# tsl2591.net
KiCad netlist of a schematic drawn in EAGLE
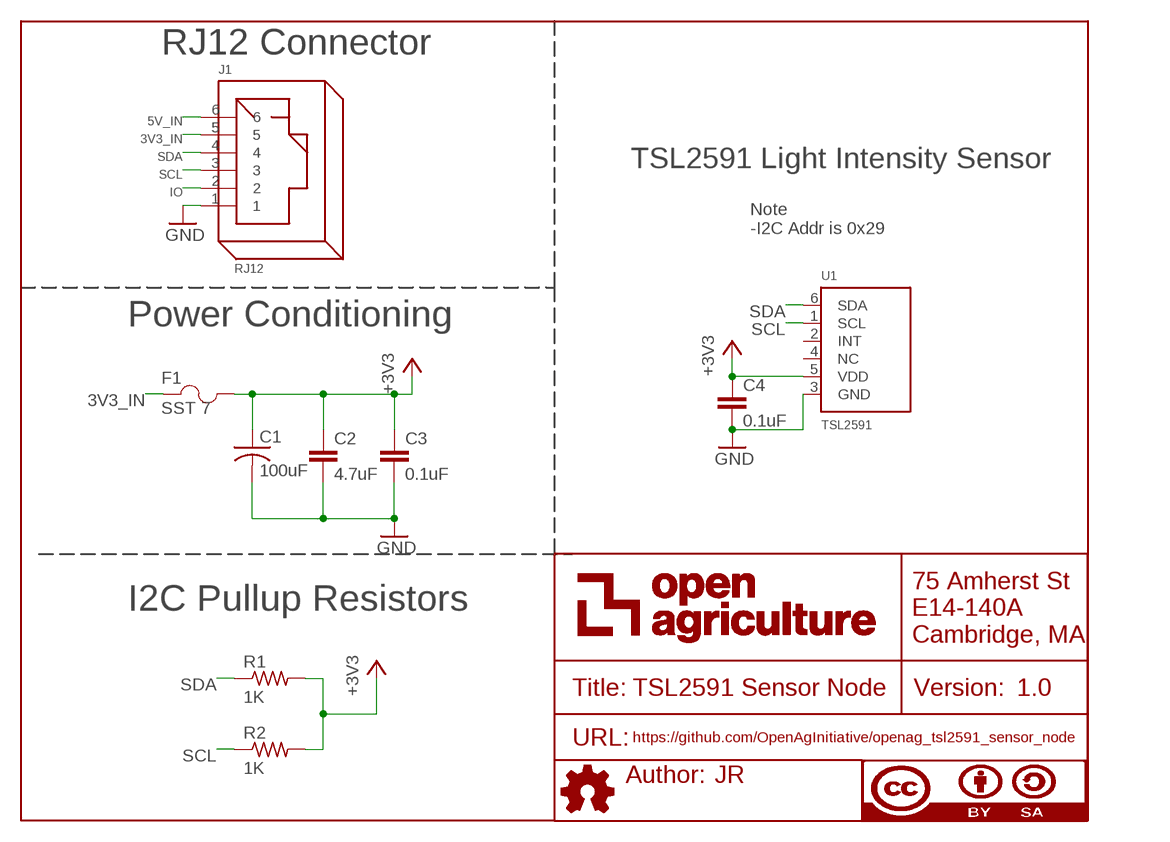
[diagram p0: schematic, sheet 1]

(export (version "E")
  (design (tool "Eeschema 10.0.6"))
  (components
    (comp (ref "C1")
      (value "100uF")
      (footprint "eagle-import:EEE-1HA101UP")
      (libsource (lib "eagle-import") (part "100UF-EEE-1HA101UP"))
    )
    (comp (ref "C2")
      (value "4.7uF")
      (footprint "eagle-import:C0805")
      (libsource (lib "eagle-import") (part "4.7UF-CL21A475KBQNNNE"))
    )
    (comp (ref "C3")
      (value "0.1uF")
      (footprint "eagle-import:C0603")
      (libsource (lib "eagle-import") (part "0.1UF-C0603C104K5RACTU"))
    )
    (comp (ref "C4")
      (value "0.1uF")
      (footprint "eagle-import:C0603")
      (libsource (lib "eagle-import") (part "0.1UF-C0603C104K5RACTU"))
    )
    (comp (ref "F1")
      (value "SST 7")
      (footprint "eagle-import:SS")
      (libsource (lib "eagle-import") (part "SST_7"))
    )
    (comp (ref "FRAME1")
      (value "DOCFIELD")
      (footprint "eagle-import:DOCFIELD")
      (description "APDS-9250 RGB/UV + Ambient Light Intensity Sensor Node")
      (fields
        (field (name "TITLE") "Example Template")
        (field (name "AUTHOR") "XX")
        (field (name "VER") "1.0")
        (field (name "URL") "https://github.com/OpenAgInitiative/openag_eagle_template")
        (field (name "AUTHOR_1") "JR")
        (field (name "TITLE_1") "TSL2591 Sensor Node")
        (field (name "URL_1") "https://github.com/OpenAgInitiative/openag_tsl2591_sensor_node")
      )
      (libsource (lib "eagle-import") (part "DOCFIELD"))
    )
    (comp (ref "J1")
      (value "RJ12")
      (footprint "eagle-import:RJ12")
      (libsource (lib "eagle-import") (part "A-2004-1-4-LP-N-R"))
    )
    (comp (ref "R1")
      (value "1K")
      (footprint "eagle-import:RC0603N")
      (libsource (lib "eagle-import") (part "1K-ERJ-PB3D1001V"))
    )
    (comp (ref "R2")
      (value "1K")
      (footprint "eagle-import:RC0603N")
      (libsource (lib "eagle-import") (part "1K-ERJ-PB3D1001V"))
    )
    (comp (ref "U1")
      (value "TSL2591")
      (footprint "eagle-import:DFN6_TAOS")
      (libsource (lib "eagle-import") (part "TSL25911FN"))
    )
  )
  (nets
    (net (code "1") (name "+3V3") (class "Default")
      (node (ref "C1") (pin "+") (pinfunction "1(+)_+") (pintype "passive"))
      (node (ref "C2") (pin "1") (pinfunction "1_1") (pintype "passive"))
      (node (ref "C3") (pin "1") (pinfunction "1_1") (pintype "passive"))
      (node (ref "C4") (pin "1") (pinfunction "1_1") (pintype "passive"))
      (node (ref "F1") (pin "2") (pinfunction "2_2") (pintype "passive"))
      (node (ref "R1") (pin "2") (pinfunction "2_2") (pintype "passive"))
      (node (ref "R2") (pin "2") (pinfunction "2_2") (pintype "passive"))
      (node (ref "U1") (pin "5") (pinfunction "VDD_5") (pintype "power_in"))
    )
    (net (code "2") (name "3V3_IN") (class "Default")
      (node (ref "F1") (pin "1") (pinfunction "1_1") (pintype "passive"))
      (node (ref "J1") (pin "5") (pinfunction "5_5") (pintype "bidirectional"))
    )
    (net (code "3") (name "5V_IN") (class "Default")
      (node (ref "J1") (pin "6") (pinfunction "6_6") (pintype "bidirectional"))
    )
    (net (code "4") (name "GND") (class "Default")
      (node (ref "C1") (pin "-") (pinfunction "2(-)_-") (pintype "passive"))
      (node (ref "C2") (pin "2") (pinfunction "2_2") (pintype "passive"))
      (node (ref "C3") (pin "2") (pinfunction "2_2") (pintype "passive"))
      (node (ref "C4") (pin "2") (pinfunction "2_2") (pintype "passive"))
      (node (ref "J1") (pin "1") (pinfunction "1_1") (pintype "bidirectional"))
      (node (ref "U1") (pin "3") (pinfunction "GND_3") (pintype "power_in"))
    )
    (net (code "5") (name "IO") (class "Default")
      (node (ref "J1") (pin "2") (pinfunction "2_2") (pintype "bidirectional"))
    )
    (net (code "6") (name "SCL") (class "Default")
      (node (ref "J1") (pin "3") (pinfunction "3_3") (pintype "bidirectional"))
      (node (ref "R2") (pin "1") (pinfunction "1_1") (pintype "passive"))
      (node (ref "U1") (pin "1") (pinfunction "SCL_1") (pintype "bidirectional"))
    )
    (net (code "7") (name "SDA") (class "Default")
      (node (ref "J1") (pin "4") (pinfunction "4_4") (pintype "bidirectional"))
      (node (ref "R1") (pin "1") (pinfunction "1_1") (pintype "passive"))
      (node (ref "U1") (pin "6") (pinfunction "SDA_6") (pintype "bidirectional"))
    )
    (net (code "8") (name "unconnected-(U1-INT-Pad2)") (class "Default")
      (node (ref "U1") (pin "2") (pinfunction "INT_2") (pintype "output"))
    )
    (net (code "9") (name "unconnected-(U1-NC-Pad4)") (class "Default")
      (node (ref "U1") (pin "4") (pinfunction "NC_4") (pintype "no_connect"))
    )
  )
)
